# MCP960XL-L0X-RL0X_EVM_v1_Eagle7_x.net
KiCad netlist of a schematic drawn in EAGLE
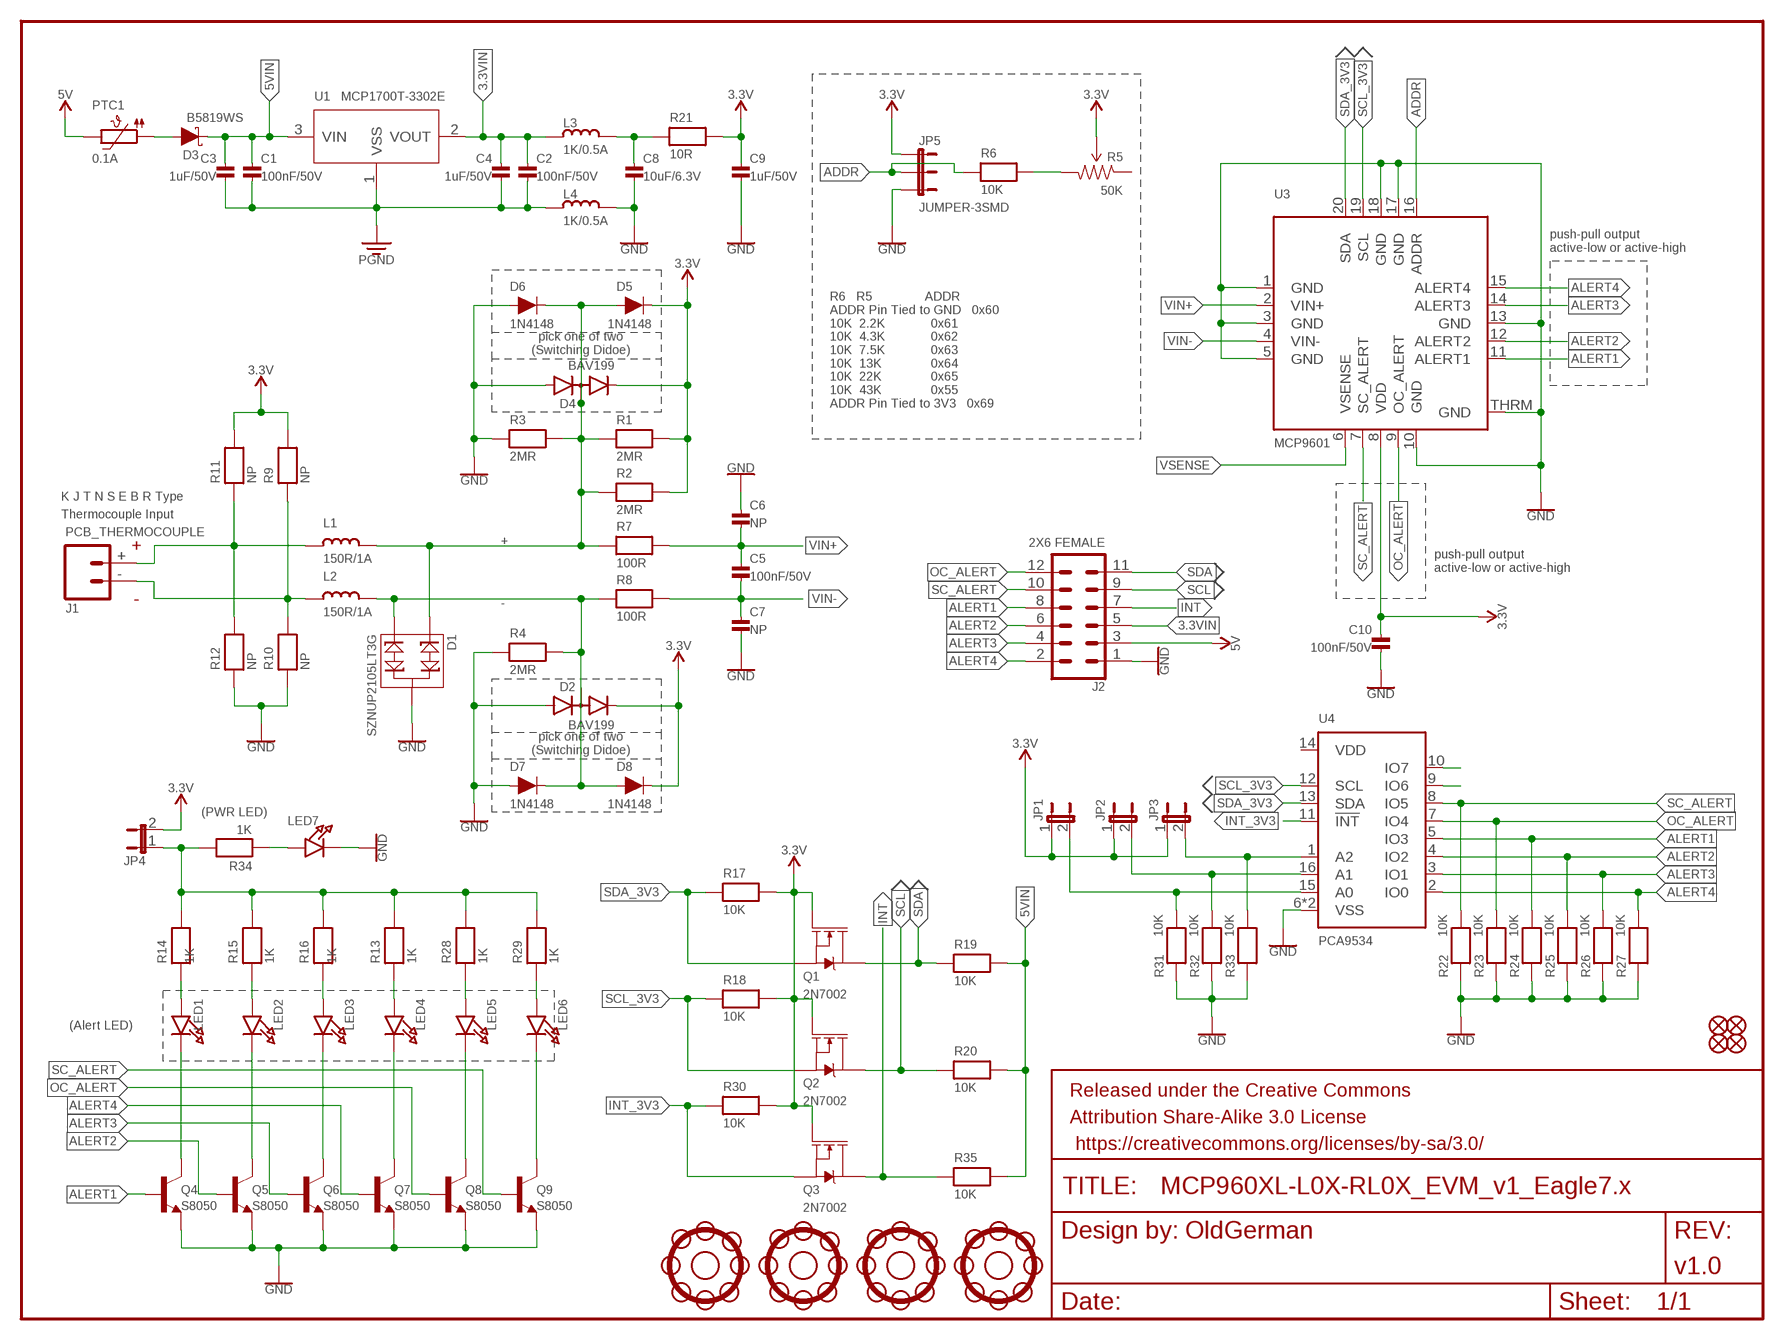
[diagram p0: schematic, sheet 1]

(export (version "E")
  (design (tool "Eeschema 10.0.6"))
  (components
    (comp (ref "C1")
      (value "100nF/50V")
      (footprint "eagle-import:0603")
      (libsource (lib "eagle-import") (part "CAP_CERAMIC0603"))
    )
    (comp (ref "C2")
      (value "100nF/50V")
      (footprint "eagle-import:0603")
      (libsource (lib "eagle-import") (part "CAP_CERAMIC0603"))
    )
    (comp (ref "C3")
      (value "1uF/50V")
      (footprint "eagle-import:0603")
      (libsource (lib "eagle-import") (part "CAP_CERAMIC0603"))
    )
    (comp (ref "C4")
      (value "1uF/50V")
      (footprint "eagle-import:0603")
      (libsource (lib "eagle-import") (part "CAP_CERAMIC0603"))
    )
    (comp (ref "C5")
      (value "100nF/50V")
      (footprint "eagle-import:0603")
      (libsource (lib "eagle-import") (part "CAP_CERAMIC0603"))
    )
    (comp (ref "C6")
      (value "NP")
      (footprint "eagle-import:0603")
      (libsource (lib "eagle-import") (part "CAP_CERAMIC0603"))
    )
    (comp (ref "C7")
      (value "NP")
      (footprint "eagle-import:0603")
      (libsource (lib "eagle-import") (part "CAP_CERAMIC0603"))
    )
    (comp (ref "C8")
      (value "10uF/6.3V")
      (footprint "eagle-import:0603")
      (libsource (lib "eagle-import") (part "CAP_CERAMIC0603"))
    )
    (comp (ref "C9")
      (value "1uF/50V")
      (footprint "eagle-import:0603")
      (libsource (lib "eagle-import") (part "CAP_CERAMIC0603"))
    )
    (comp (ref "C10")
      (value "100nF/50V")
      (footprint "eagle-import:0603")
      (libsource (lib "eagle-import") (part "CAP_CERAMIC0603"))
    )
    (comp (ref "D1")
      (value "SZNUP2105LT3G")
      (footprint "eagle-import:SOT23-3")
      (libsource (lib "eagle-import") (part "SZNUP2105LT3G"))
    )
    (comp (ref "D2")
      (value "BAV199")
      (footprint "eagle-import:SOT23-3")
      (libsource (lib "eagle-import") (part "BAV199"))
    )
    (comp (ref "D3")
      (value "B5819WS")
      (footprint "eagle-import:SOD-323")
      (libsource (lib "eagle-import") (part "DIODE_SCHOTTKYSOD323"))
    )
    (comp (ref "D4")
      (value "BAV199")
      (footprint "eagle-import:SOT23-3")
      (libsource (lib "eagle-import") (part "BAV199"))
    )
    (comp (ref "D5")
      (value "1N4148")
      (footprint "eagle-import:SOD-323")
      (libsource (lib "eagle-import") (part "DIODE"))
    )
    (comp (ref "D6")
      (value "1N4148")
      (footprint "eagle-import:SOD-323")
      (libsource (lib "eagle-import") (part "DIODE"))
    )
    (comp (ref "D7")
      (value "1N4148")
      (footprint "eagle-import:SOD-323")
      (libsource (lib "eagle-import") (part "DIODE"))
    )
    (comp (ref "D8")
      (value "1N4148")
      (footprint "eagle-import:SOD-323")
      (libsource (lib "eagle-import") (part "DIODE"))
    )
    (comp (ref "FID1")
      (value "FIDUCIAL1X2.5")
      (footprint "eagle-import:FIDUCIAL-1X2.5")
      (libsource (lib "eagle-import") (part "FIDUCIAL1X2.5"))
    )
    (comp (ref "FID2")
      (value "FIDUCIAL1X2.5")
      (footprint "eagle-import:FIDUCIAL-1X2.5")
      (libsource (lib "eagle-import") (part "FIDUCIAL1X2.5"))
    )
    (comp (ref "FID3")
      (value "FIDUCIAL1X2.5")
      (footprint "eagle-import:FIDUCIAL-1X2.5")
      (libsource (lib "eagle-import") (part "FIDUCIAL1X2.5"))
    )
    (comp (ref "FID4")
      (value "FIDUCIAL1X2.5")
      (footprint "eagle-import:FIDUCIAL-1X2.5")
      (libsource (lib "eagle-import") (part "FIDUCIAL1X2.5"))
    )
    (comp (ref "FRAME1")
      (value "FRAME-LETTER")
      (footprint "eagle-import:CREATIVE_COMMONS")
      (libsource (lib "eagle-import") (part "FRAME-LETTER"))
    )
    (comp (ref "J1")
      (value "PCB_THERMOCOUPLE")
      (footprint "eagle-import:PCC-SMP")
      (libsource (lib "eagle-import") (part "PCB_THERMOCOUPLE"))
    )
    (comp (ref "J2")
      (value "2X6 FEMALE")
      (footprint "eagle-import:2X6")
      (libsource (lib "eagle-import") (part "CONN_06X2PTH_FEMALE"))
    )
    (comp (ref "JP1")
      (value "JUMPER-2SMD-NC")
      (footprint "eagle-import:SJ_2S")
      (libsource (lib "eagle-import") (part "JUMPER-2SMD-NC"))
    )
    (comp (ref "JP2")
      (value "JUMPER-2SMD-NC")
      (footprint "eagle-import:SJ_2S")
      (libsource (lib "eagle-import") (part "JUMPER-2SMD-NC"))
    )
    (comp (ref "JP3")
      (value "JUMPER-2SMD-NC")
      (footprint "eagle-import:SJ_2S")
      (libsource (lib "eagle-import") (part "JUMPER-2SMD-NC"))
    )
    (comp (ref "JP4")
      (value "JUMPER-2SMD-NC")
      (footprint "eagle-import:SJ_2S")
      (libsource (lib "eagle-import") (part "JUMPER-2SMD-NC"))
    )
    (comp (ref "JP5")
      (value "JUMPER-3SMD")
      (footprint "eagle-import:SJ_3")
      (libsource (lib "eagle-import") (part "JUMPER-3SMD"))
    )
    (comp (ref "L1")
      (value "150R/1A")
      (footprint "eagle-import:0603")
      (libsource (lib "eagle-import") (part "INDUCTOR0603"))
    )
    (comp (ref "L2")
      (value "150R/1A")
      (footprint "eagle-import:0603")
      (libsource (lib "eagle-import") (part "INDUCTOR0603"))
    )
    (comp (ref "L3")
      (value "1K/0.5A")
      (footprint "eagle-import:0603")
      (libsource (lib "eagle-import") (part "INDUCTOR0603"))
    )
    (comp (ref "L4")
      (value "1K/0.5A")
      (footprint "eagle-import:0603")
      (libsource (lib "eagle-import") (part "INDUCTOR0603"))
    )
    (comp (ref "LED1")
      (value "LED0603")
      (footprint "eagle-import:CHIPLED_0603")
      (libsource (lib "eagle-import") (part "LED0603"))
    )
    (comp (ref "LED2")
      (value "LED0603")
      (footprint "eagle-import:CHIPLED_0603")
      (libsource (lib "eagle-import") (part "LED0603"))
    )
    (comp (ref "LED3")
      (value "LED0603")
      (footprint "eagle-import:CHIPLED_0603")
      (libsource (lib "eagle-import") (part "LED0603"))
    )
    (comp (ref "LED4")
      (value "LED0603")
      (footprint "eagle-import:CHIPLED_0603")
      (libsource (lib "eagle-import") (part "LED0603"))
    )
    (comp (ref "LED5")
      (value "LED0603")
      (footprint "eagle-import:CHIPLED_0603")
      (libsource (lib "eagle-import") (part "LED0603"))
    )
    (comp (ref "LED6")
      (value "LED0603")
      (footprint "eagle-import:CHIPLED_0603")
      (libsource (lib "eagle-import") (part "LED0603"))
    )
    (comp (ref "LED7")
      (value "LED0603")
      (footprint "eagle-import:CHIPLED_0603")
      (libsource (lib "eagle-import") (part "LED0603"))
    )
    (comp (ref "PTC1")
      (value "0.1A")
      (footprint "eagle-import:1206")
      (libsource (lib "eagle-import") (part "PTC1206"))
    )
    (comp (ref "Q1")
      (value "2N7002")
      (footprint "eagle-import:SOT23-3")
      (libsource (lib "eagle-import") (part "MOSFET-NCH-AO3404A"))
    )
    (comp (ref "Q2")
      (value "2N7002")
      (footprint "eagle-import:SOT23-3")
      (libsource (lib "eagle-import") (part "MOSFET-NCH-AO3404A"))
    )
    (comp (ref "Q3")
      (value "2N7002")
      (footprint "eagle-import:SOT23-3")
      (libsource (lib "eagle-import") (part "MOSFET-NCH-AO3404A"))
    )
    (comp (ref "Q4")
      (value "S8050")
      (footprint "eagle-import:SOT23-3")
      (libsource (lib "eagle-import") (part "TRANS_NPN-MMBT2222AL"))
    )
    (comp (ref "Q5")
      (value "S8050")
      (footprint "eagle-import:SOT23-3")
      (libsource (lib "eagle-import") (part "TRANS_NPN-MMBT2222AL"))
    )
    (comp (ref "Q6")
      (value "S8050")
      (footprint "eagle-import:SOT23-3")
      (libsource (lib "eagle-import") (part "TRANS_NPN-MMBT2222AL"))
    )
    (comp (ref "Q7")
      (value "S8050")
      (footprint "eagle-import:SOT23-3")
      (libsource (lib "eagle-import") (part "TRANS_NPN-MMBT2222AL"))
    )
    (comp (ref "Q8")
      (value "S8050")
      (footprint "eagle-import:SOT23-3")
      (libsource (lib "eagle-import") (part "TRANS_NPN-MMBT2222AL"))
    )
    (comp (ref "Q9")
      (value "S8050")
      (footprint "eagle-import:SOT23-3")
      (libsource (lib "eagle-import") (part "TRANS_NPN-MMBT2222AL"))
    )
    (comp (ref "R1")
      (value "2MR")
      (footprint "eagle-import:0603")
      (libsource (lib "eagle-import") (part "RESISTOR0603"))
    )
    (comp (ref "R2")
      (value "2MR")
      (footprint "eagle-import:0603")
      (libsource (lib "eagle-import") (part "RESISTOR0603"))
    )
    (comp (ref "R3")
      (value "2MR")
      (footprint "eagle-import:0603")
      (libsource (lib "eagle-import") (part "RESISTOR0603"))
    )
    (comp (ref "R4")
      (value "2MR")
      (footprint "eagle-import:0603")
      (libsource (lib "eagle-import") (part "RESISTOR0603"))
    )
    (comp (ref "R5")
      (value "50K")
      (footprint "eagle-import:TRIMPOT-3MM")
      (libsource (lib "eagle-import") (part "POT-SMD"))
    )
    (comp (ref "R6")
      (value "10K")
      (footprint "eagle-import:0603")
      (libsource (lib "eagle-import") (part "RESISTOR0603"))
    )
    (comp (ref "R7")
      (value "100R")
      (footprint "eagle-import:0603")
      (libsource (lib "eagle-import") (part "RESISTOR0603"))
    )
    (comp (ref "R8")
      (value "100R")
      (footprint "eagle-import:0603")
      (libsource (lib "eagle-import") (part "RESISTOR0603"))
    )
    (comp (ref "R9")
      (value "NP")
      (footprint "eagle-import:0603")
      (libsource (lib "eagle-import") (part "RESISTOR0603"))
    )
    (comp (ref "R10")
      (value "NP")
      (footprint "eagle-import:0603")
      (libsource (lib "eagle-import") (part "RESISTOR0603"))
    )
    (comp (ref "R11")
      (value "NP")
      (footprint "eagle-import:0603")
      (libsource (lib "eagle-import") (part "RESISTOR0603"))
    )
    (comp (ref "R12")
      (value "NP")
      (footprint "eagle-import:0603")
      (libsource (lib "eagle-import") (part "RESISTOR0603"))
    )
    (comp (ref "R13")
      (value "1K")
      (footprint "eagle-import:0603")
      (libsource (lib "eagle-import") (part "RESISTOR0603"))
    )
    (comp (ref "R14")
      (value "1K")
      (footprint "eagle-import:0603")
      (libsource (lib "eagle-import") (part "RESISTOR0603"))
    )
    (comp (ref "R15")
      (value "1K")
      (footprint "eagle-import:0603")
      (libsource (lib "eagle-import") (part "RESISTOR0603"))
    )
    (comp (ref "R16")
      (value "1K")
      (footprint "eagle-import:0603")
      (libsource (lib "eagle-import") (part "RESISTOR0603"))
    )
    (comp (ref "R17")
      (value "10K")
      (footprint "eagle-import:0603")
      (libsource (lib "eagle-import") (part "RESISTOR0603"))
    )
    (comp (ref "R18")
      (value "10K")
      (footprint "eagle-import:0603")
      (libsource (lib "eagle-import") (part "RESISTOR0603"))
    )
    (comp (ref "R19")
      (value "10K")
      (footprint "eagle-import:0603")
      (libsource (lib "eagle-import") (part "RESISTOR0603"))
    )
    (comp (ref "R20")
      (value "10K")
      (footprint "eagle-import:0603")
      (libsource (lib "eagle-import") (part "RESISTOR0603"))
    )
    (comp (ref "R21")
      (value "10R")
      (footprint "eagle-import:0603")
      (libsource (lib "eagle-import") (part "RESISTOR0603"))
    )
    (comp (ref "R22")
      (value "10K")
      (footprint "eagle-import:0603")
      (libsource (lib "eagle-import") (part "RESISTOR0603"))
    )
    (comp (ref "R23")
      (value "10K")
      (footprint "eagle-import:0603")
      (libsource (lib "eagle-import") (part "RESISTOR0603"))
    )
    (comp (ref "R24")
      (value "10K")
      (footprint "eagle-import:0603")
      (libsource (lib "eagle-import") (part "RESISTOR0603"))
    )
    (comp (ref "R25")
      (value "10K")
      (footprint "eagle-import:0603")
      (libsource (lib "eagle-import") (part "RESISTOR0603"))
    )
    (comp (ref "R26")
      (value "10K")
      (footprint "eagle-import:0603")
      (libsource (lib "eagle-import") (part "RESISTOR0603"))
    )
    (comp (ref "R27")
      (value "10K")
      (footprint "eagle-import:0603")
      (libsource (lib "eagle-import") (part "RESISTOR0603"))
    )
    (comp (ref "R28")
      (value "1K")
      (footprint "eagle-import:0603")
      (libsource (lib "eagle-import") (part "RESISTOR0603"))
    )
    (comp (ref "R29")
      (value "1K")
      (footprint "eagle-import:0603")
      (libsource (lib "eagle-import") (part "RESISTOR0603"))
    )
    (comp (ref "R30")
      (value "10K")
      (footprint "eagle-import:0603")
      (libsource (lib "eagle-import") (part "RESISTOR0603"))
    )
    (comp (ref "R31")
      (value "10K")
      (footprint "eagle-import:0603")
      (libsource (lib "eagle-import") (part "RESISTOR0603"))
    )
    (comp (ref "R32")
      (value "10K")
      (footprint "eagle-import:0603")
      (libsource (lib "eagle-import") (part "RESISTOR0603"))
    )
    (comp (ref "R33")
      (value "10K")
      (footprint "eagle-import:0603")
      (libsource (lib "eagle-import") (part "RESISTOR0603"))
    )
    (comp (ref "R34")
      (value "1K")
      (footprint "eagle-import:0603")
      (libsource (lib "eagle-import") (part "RESISTOR0603"))
    )
    (comp (ref "R35")
      (value "10K")
      (footprint "eagle-import:0603")
      (libsource (lib "eagle-import") (part "RESISTOR0603"))
    )
    (comp (ref "U$1")
      (value "SUN_HOLE_M3")
      (footprint "eagle-import:SUN_HOLE_M3")
      (libsource (lib "eagle-import") (part "SUN_HOLE_M3"))
    )
    (comp (ref "U$3")
      (value "SUN_HOLE_M3")
      (footprint "eagle-import:SUN_HOLE_M3")
      (libsource (lib "eagle-import") (part "SUN_HOLE_M3"))
    )
    (comp (ref "U$4")
      (value "SUN_HOLE_M3")
      (footprint "eagle-import:SUN_HOLE_M3")
      (libsource (lib "eagle-import") (part "SUN_HOLE_M3"))
    )
    (comp (ref "U$6")
      (value "SUN_HOLE_M3")
      (footprint "eagle-import:SUN_HOLE_M3")
      (libsource (lib "eagle-import") (part "SUN_HOLE_M3"))
    )
    (comp (ref "U1")
      (value "MCP1700T-3302E")
      (footprint "eagle-import:SOT23-3")
      (libsource (lib "eagle-import") (part "LDO_3PIN"))
    )
    (comp (ref "U3")
      (value "MCP9601")
      (footprint "eagle-import:VQFN20_5MM")
      (libsource (lib "eagle-import") (part "MCP9601"))
    )
    (comp (ref "U4")
      (value "PCA9534")
      (footprint "eagle-import:HVQFN16_4X4_0.65MM")
      (libsource (lib "eagle-import") (part "PCA9534"))
    )
  )
  (nets
    (net (code "1") (name "/VDD") (class "Default")
      (node (ref "U4") (pin "14") (pinfunction "VDD_14") (pintype "power_in"))
    )
    (net (code "2") (name "3.3V") (class "Default")
      (node (ref "C10") (pin "1") (pinfunction "P$1_1") (pintype "passive"))
      (node (ref "C9") (pin "1") (pinfunction "P$1_1") (pintype "passive"))
      (node (ref "D2") (pin "3") (pinfunction "C_3") (pintype "passive"))
      (node (ref "D4") (pin "3") (pinfunction "C_3") (pintype "passive"))
      (node (ref "D5") (pin "C") (pinfunction "C_C") (pintype "passive"))
      (node (ref "D8") (pin "C") (pinfunction "C_C") (pintype "passive"))
      (node (ref "JP1") (pin "1") (pinfunction "1_1") (pintype "passive"))
      (node (ref "JP2") (pin "1") (pinfunction "1_1") (pintype "passive"))
      (node (ref "JP3") (pin "1") (pinfunction "1_1") (pintype "passive"))
      (node (ref "JP4") (pin "2") (pinfunction "2_2") (pintype "passive"))
      (node (ref "JP5") (pin "1") (pinfunction "1_1") (pintype "passive"))
      (node (ref "Q1") (pin "1") (pinfunction "G_1") (pintype "bidirectional"))
      (node (ref "Q2") (pin "1") (pinfunction "G_1") (pintype "bidirectional"))
      (node (ref "Q3") (pin "1") (pinfunction "G_1") (pintype "bidirectional"))
      (node (ref "R1") (pin "2") (pinfunction "2_2") (pintype "passive"))
      (node (ref "R11") (pin "2") (pinfunction "2_2") (pintype "passive"))
      (node (ref "R17") (pin "2") (pinfunction "2_2") (pintype "passive"))
      (node (ref "R18") (pin "2") (pinfunction "2_2") (pintype "passive"))
      (node (ref "R2") (pin "2") (pinfunction "2_2") (pintype "passive"))
      (node (ref "R21") (pin "2") (pinfunction "2_2") (pintype "passive"))
      (node (ref "R30") (pin "2") (pinfunction "2_2") (pintype "passive"))
      (node (ref "R5") (pin "2") (pinfunction "WIPER_2") (pintype "passive"))
      (node (ref "R9") (pin "2") (pinfunction "2_2") (pintype "passive"))
      (node (ref "U3") (pin "8") (pinfunction "VDD_8") (pintype "bidirectional"))
    )
    (net (code "3") (name "3.3VIN") (class "Default")
      (node (ref "C2") (pin "1") (pinfunction "P$1_1") (pintype "passive"))
      (node (ref "C4") (pin "1") (pinfunction "P$1_1") (pintype "passive"))
      (node (ref "J2") (pin "5") (pinfunction "5_5") (pintype "passive"))
      (node (ref "L3") (pin "1") (pinfunction "1_1") (pintype "passive"))
      (node (ref "U1") (pin "2") (pinfunction "VOUT_2") (pintype "bidirectional"))
    )
    (net (code "4") (name "5V") (class "Default")
      (node (ref "J2") (pin "3") (pinfunction "3_3") (pintype "passive"))
      (node (ref "PTC1") (pin "2") (pinfunction "2_2") (pintype "passive"))
    )
    (net (code "5") (name "5VIN") (class "Default")
      (node (ref "C1") (pin "1") (pinfunction "P$1_1") (pintype "passive"))
      (node (ref "C3") (pin "1") (pinfunction "P$1_1") (pintype "passive"))
      (node (ref "D3") (pin "C") (pinfunction "C_C") (pintype "passive"))
      (node (ref "R19") (pin "2") (pinfunction "2_2") (pintype "passive"))
      (node (ref "R20") (pin "2") (pinfunction "2_2") (pintype "passive"))
      (node (ref "R35") (pin "2") (pinfunction "2_2") (pintype "passive"))
      (node (ref "U1") (pin "3") (pinfunction "VIN_3") (pintype "bidirectional"))
    )
    (net (code "6") (name "ADDR") (class "Default")
      (node (ref "JP5") (pin "2") (pinfunction "2_2") (pintype "passive"))
      (node (ref "R6") (pin "1") (pinfunction "1_1") (pintype "passive"))
      (node (ref "U3") (pin "16") (pinfunction "ADDR_16") (pintype "bidirectional"))
    )
    (net (code "7") (name "ALERT1") (class "Default")
      (node (ref "J2") (pin "8") (pinfunction "8_8") (pintype "passive"))
      (node (ref "Q4") (pin "1") (pinfunction "B_1") (pintype "passive"))
      (node (ref "R24") (pin "2") (pinfunction "2_2") (pintype "passive"))
      (node (ref "U3") (pin "11") (pinfunction "ALERT1_11") (pintype "bidirectional"))
      (node (ref "U4") (pin "5") (pinfunction "IO3_5") (pintype "bidirectional"))
    )
    (net (code "8") (name "ALERT2") (class "Default")
      (node (ref "J2") (pin "6") (pinfunction "6_6") (pintype "passive"))
      (node (ref "Q5") (pin "1") (pinfunction "B_1") (pintype "passive"))
      (node (ref "R25") (pin "2") (pinfunction "2_2") (pintype "passive"))
      (node (ref "U3") (pin "12") (pinfunction "ALERT2_12") (pintype "bidirectional"))
      (node (ref "U4") (pin "4") (pinfunction "IO2_4") (pintype "bidirectional"))
    )
    (net (code "9") (name "ALERT3") (class "Default")
      (node (ref "J2") (pin "4") (pinfunction "4_4") (pintype "passive"))
      (node (ref "Q6") (pin "1") (pinfunction "B_1") (pintype "passive"))
      (node (ref "R26") (pin "2") (pinfunction "2_2") (pintype "passive"))
      (node (ref "U3") (pin "14") (pinfunction "ALERT3_14") (pintype "bidirectional"))
      (node (ref "U4") (pin "3") (pinfunction "IO1_3") (pintype "bidirectional"))
    )
    (net (code "10") (name "ALERT4") (class "Default")
      (node (ref "J2") (pin "2") (pinfunction "2_2") (pintype "passive"))
      (node (ref "Q7") (pin "1") (pinfunction "B_1") (pintype "passive"))
      (node (ref "R27") (pin "2") (pinfunction "2_2") (pintype "passive"))
      (node (ref "U3") (pin "15") (pinfunction "ALERT4_15") (pintype "bidirectional"))
      (node (ref "U4") (pin "2") (pinfunction "IO0_2") (pintype "bidirectional"))
    )
    (net (code "11") (name "GND") (class "Default")
      (node (ref "C10") (pin "2") (pinfunction "P$2_2") (pintype "passive"))
      (node (ref "C6") (pin "1") (pinfunction "P$1_1") (pintype "passive"))
      (node (ref "C7") (pin "2") (pinfunction "P$2_2") (pintype "passive"))
      (node (ref "C8") (pin "2") (pinfunction "P$2_2") (pintype "passive"))
      (node (ref "C9") (pin "2") (pinfunction "P$2_2") (pintype "passive"))
      (node (ref "D1") (pin "3") (pinfunction "3_3") (pintype "bidirectional"))
      (node (ref "D2") (pin "1") (pinfunction "A_1") (pintype "passive"))
      (node (ref "D4") (pin "1") (pinfunction "A_1") (pintype "passive"))
      (node (ref "D6") (pin "A") (pinfunction "A_A") (pintype "passive"))
      (node (ref "D7") (pin "A") (pinfunction "A_A") (pintype "passive"))
      (node (ref "J2") (pin "1") (pinfunction "1_1") (pintype "passive"))
      (node (ref "JP5") (pin "3") (pinfunction "3_3") (pintype "passive"))
      (node (ref "L4") (pin "2") (pinfunction "2_2") (pintype "passive"))
      (node (ref "LED7") (pin "C") (pinfunction "C_C") (pintype "passive"))
      (node (ref "Q4") (pin "2") (pinfunction "E_2") (pintype "passive"))
      (node (ref "Q5") (pin "2") (pinfunction "E_2") (pintype "passive"))
      (node (ref "Q6") (pin "2") (pinfunction "E_2") (pintype "passive"))
      (node (ref "Q7") (pin "2") (pinfunction "E_2") (pintype "passive"))
      (node (ref "Q8") (pin "2") (pinfunction "E_2") (pintype "passive"))
      (node (ref "Q9") (pin "2") (pinfunction "E_2") (pintype "passive"))
      (node (ref "R10") (pin "1") (pinfunction "1_1") (pintype "passive"))
      (node (ref "R12") (pin "1") (pinfunction "1_1") (pintype "passive"))
      (node (ref "R22") (pin "1") (pinfunction "1_1") (pintype "passive"))
      (node (ref "R23") (pin "1") (pinfunction "1_1") (pintype "passive"))
      (node (ref "R24") (pin "1") (pinfunction "1_1") (pintype "passive"))
      (node (ref "R25") (pin "1") (pinfunction "1_1") (pintype "passive"))
      (node (ref "R26") (pin "1") (pinfunction "1_1") (pintype "passive"))
      (node (ref "R27") (pin "1") (pinfunction "1_1") (pintype "passive"))
      (node (ref "R3") (pin "1") (pinfunction "1_1") (pintype "passive"))
      (node (ref "R31") (pin "1") (pinfunction "1_1") (pintype "passive"))
      (node (ref "R32") (pin "1") (pinfunction "1_1") (pintype "passive"))
      (node (ref "R33") (pin "1") (pinfunction "1_1") (pintype "passive"))
      (node (ref "R4") (pin "1") (pinfunction "1_1") (pintype "passive"))
      (node (ref "U3") (pin "1") (pinfunction "GND_1") (pintype "bidirectional"))
      (node (ref "U3") (pin "10") (pinfunction "GND_10") (pintype "bidirectional"))
      (node (ref "U3") (pin "13") (pinfunction "GND_13") (pintype "bidirectional"))
      (node (ref "U3") (pin "17") (pinfunction "GND_17") (pintype "bidirectional"))
      (node (ref "U3") (pin "18") (pinfunction "GND_18") (pintype "bidirectional"))
      (node (ref "U3") (pin "3") (pinfunction "GND_3") (pintype "bidirectional"))
      (node (ref "U3") (pin "5") (pinfunction "GND_5") (pintype "bidirectional"))
      (node (ref "U3") (pin "THRM") (pinfunction "GND_THRM") (pintype "bidirectional"))
      (node (ref "U4") (pin "6") (pinfunction "VSS_6") (pintype "power_in"))
      (node (ref "U4") (pin "PAD") (pinfunction "VSS_PAD") (pintype "power_in"))
    )
    (net (code "12") (name "INT") (class "Default")
      (node (ref "J2") (pin "7") (pinfunction "7_7") (pintype "passive"))
      (node (ref "Q3") (pin "3") (pinfunction "D_3") (pintype "bidirectional"))
      (node (ref "R35") (pin "1") (pinfunction "1_1") (pintype "passive"))
    )
    (net (code "13") (name "INT_3V3") (class "Default")
      (node (ref "Q3") (pin "2") (pinfunction "S_2") (pintype "bidirectional"))
      (node (ref "R30") (pin "1") (pinfunction "1_1") (pintype "passive"))
      (node (ref "U4") (pin "11") (pinfunction "~{INT}_11") (pintype "open_collector"))
    )
    (net (code "14") (name "Net-(C8-P$1)") (class "Default")
      (node (ref "C8") (pin "1") (pinfunction "P$1_1") (pintype "passive"))
      (node (ref "L3") (pin "2") (pinfunction "2_2") (pintype "passive"))
      (node (ref "R21") (pin "1") (pinfunction "1_1") (pintype "passive"))
    )
    (net (code "15") (name "Net-(D2-AC)") (class "Default")
      (node (ref "D1") (pin "2") (pinfunction "2_2") (pintype "power_in"))
      (node (ref "D2") (pin "2") (pinfunction "AC_2") (pintype "passive"))
      (node (ref "D7") (pin "C") (pinfunction "C_C") (pintype "passive"))
      (node (ref "D8") (pin "A") (pinfunction "A_A") (pintype "passive"))
      (node (ref "L2") (pin "2") (pinfunction "2_2") (pintype "passive"))
      (node (ref "R4") (pin "2") (pinfunction "2_2") (pintype "passive"))
      (node (ref "R8") (pin "1") (pinfunction "1_1") (pintype "passive"))
    )
    (net (code "16") (name "Net-(D3-PadA)") (class "Default")
      (node (ref "D3") (pin "A") (pinfunction "A_A") (pintype "passive"))
      (node (ref "PTC1") (pin "1") (pinfunction "1_1") (pintype "passive"))
    )
    (net (code "17") (name "Net-(D4-AC)") (class "Default")
      (node (ref "D1") (pin "1") (pinfunction "1_1") (pintype "power_in"))
      (node (ref "D4") (pin "2") (pinfunction "AC_2") (pintype "passive"))
      (node (ref "D5") (pin "A") (pinfunction "A_A") (pintype "passive"))
      (node (ref "D6") (pin "C") (pinfunction "C_C") (pintype "passive"))
      (node (ref "L1") (pin "2") (pinfunction "2_2") (pintype "passive"))
      (node (ref "R1") (pin "1") (pinfunction "1_1") (pintype "passive"))
      (node (ref "R2") (pin "1") (pinfunction "1_1") (pintype "passive"))
      (node (ref "R3") (pin "2") (pinfunction "2_2") (pintype "passive"))
      (node (ref "R7") (pin "1") (pinfunction "1_1") (pintype "passive"))
    )
    (net (code "18") (name "Net-(J1-Pad+)") (class "Default")
      (node (ref "J1") (pin "+") (pinfunction "+_+") (pintype "passive"))
      (node (ref "L1") (pin "1") (pinfunction "1_1") (pintype "passive"))
      (node (ref "R11") (pin "1") (pinfunction "1_1") (pintype "passive"))
      (node (ref "R12") (pin "2") (pinfunction "2_2") (pintype "passive"))
    )
    (net (code "19") (name "Net-(J1-Pad-)") (class "Default")
      (node (ref "J1") (pin "-") (pinfunction "-_-") (pintype "passive"))
      (node (ref "L2") (pin "1") (pinfunction "1_1") (pintype "passive"))
      (node (ref "R10") (pin "2") (pinfunction "2_2") (pintype "passive"))
      (node (ref "R9") (pin "1") (pinfunction "1_1") (pintype "passive"))
    )
    (net (code "20") (name "Net-(JP4-Pad1)") (class "Default")
      (node (ref "JP4") (pin "1") (pinfunction "1_1") (pintype "passive"))
      (node (ref "R13") (pin "2") (pinfunction "2_2") (pintype "passive"))
      (node (ref "R14") (pin "2") (pinfunction "2_2") (pintype "passive"))
      (node (ref "R15") (pin "2") (pinfunction "2_2") (pintype "passive"))
      (node (ref "R16") (pin "2") (pinfunction "2_2") (pintype "passive"))
      (node (ref "R28") (pin "2") (pinfunction "2_2") (pintype "passive"))
      (node (ref "R29") (pin "2") (pinfunction "2_2") (pintype "passive"))
      (node (ref "R34") (pin "2") (pinfunction "2_2") (pintype "passive"))
    )
    (net (code "21") (name "Net-(LED1-PadA)") (class "Default")
      (node (ref "LED1") (pin "A") (pinfunction "A_A") (pintype "passive"))
      (node (ref "R14") (pin "1") (pinfunction "1_1") (pintype "passive"))
    )
    (net (code "22") (name "Net-(LED2-PadA)") (class "Default")
      (node (ref "LED2") (pin "A") (pinfunction "A_A") (pintype "passive"))
      (node (ref "R15") (pin "1") (pinfunction "1_1") (pintype "passive"))
    )
    (net (code "23") (name "Net-(LED3-PadA)") (class "Default")
      (node (ref "LED3") (pin "A") (pinfunction "A_A") (pintype "passive"))
      (node (ref "R16") (pin "1") (pinfunction "1_1") (pintype "passive"))
    )
    (net (code "24") (name "Net-(LED4-PadA)") (class "Default")
      (node (ref "LED4") (pin "A") (pinfunction "A_A") (pintype "passive"))
      (node (ref "R13") (pin "1") (pinfunction "1_1") (pintype "passive"))
    )
    (net (code "25") (name "Net-(LED5-PadA)") (class "Default")
      (node (ref "LED5") (pin "A") (pinfunction "A_A") (pintype "passive"))
      (node (ref "R28") (pin "1") (pinfunction "1_1") (pintype "passive"))
    )
    (net (code "26") (name "Net-(LED6-PadA)") (class "Default")
      (node (ref "LED6") (pin "A") (pinfunction "A_A") (pintype "passive"))
      (node (ref "R29") (pin "1") (pinfunction "1_1") (pintype "passive"))
    )
    (net (code "27") (name "Net-(LED7-PadA)") (class "Default")
      (node (ref "LED7") (pin "A") (pinfunction "A_A") (pintype "passive"))
      (node (ref "R34") (pin "1") (pinfunction "1_1") (pintype "passive"))
    )
    (net (code "28") (name "Net-(Q4-C)") (class "Default")
      (node (ref "LED1") (pin "C") (pinfunction "C_C") (pintype "passive"))
      (node (ref "Q4") (pin "3") (pinfunction "C_3") (pintype "passive"))
    )
    (net (code "29") (name "Net-(Q5-C)") (class "Default")
      (node (ref "LED2") (pin "C") (pinfunction "C_C") (pintype "passive"))
      (node (ref "Q5") (pin "3") (pinfunction "C_3") (pintype "passive"))
    )
    (net (code "30") (name "Net-(Q6-C)") (class "Default")
      (node (ref "LED3") (pin "C") (pinfunction "C_C") (pintype "passive"))
      (node (ref "Q6") (pin "3") (pinfunction "C_3") (pintype "passive"))
    )
    (net (code "31") (name "Net-(Q7-C)") (class "Default")
      (node (ref "LED4") (pin "C") (pinfunction "C_C") (pintype "passive"))
      (node (ref "Q7") (pin "3") (pinfunction "C_3") (pintype "passive"))
    )
    (net (code "32") (name "Net-(Q8-C)") (class "Default")
      (node (ref "LED5") (pin "C") (pinfunction "C_C") (pintype "passive"))
      (node (ref "Q8") (pin "3") (pinfunction "C_3") (pintype "passive"))
    )
    (net (code "33") (name "Net-(Q9-C)") (class "Default")
      (node (ref "LED6") (pin "C") (pinfunction "C_C") (pintype "passive"))
      (node (ref "Q9") (pin "3") (pinfunction "C_3") (pintype "passive"))
    )
    (net (code "34") (name "Net-(R5-CW)") (class "Default")
      (node (ref "R5") (pin "1") (pinfunction "CW_1") (pintype "passive"))
      (node (ref "R6") (pin "2") (pinfunction "2_2") (pintype "passive"))
    )
    (net (code "35") (name "Net-(U4-A0)") (class "Default")
      (node (ref "JP1") (pin "2") (pinfunction "2_2") (pintype "passive"))
      (node (ref "R31") (pin "2") (pinfunction "2_2") (pintype "passive"))
      (node (ref "U4") (pin "15") (pinfunction "A0_15") (pintype "input"))
    )
    (net (code "36") (name "Net-(U4-A1)") (class "Default")
      (node (ref "JP2") (pin "2") (pinfunction "2_2") (pintype "passive"))
      (node (ref "R32") (pin "2") (pinfunction "2_2") (pintype "passive"))
      (node (ref "U4") (pin "16") (pinfunction "A1_16") (pintype "input"))
    )
    (net (code "37") (name "Net-(U4-A2)") (class "Default")
      (node (ref "JP3") (pin "2") (pinfunction "2_2") (pintype "passive"))
      (node (ref "R33") (pin "2") (pinfunction "2_2") (pintype "passive"))
      (node (ref "U4") (pin "1") (pinfunction "A2_1") (pintype "input"))
    )
    (net (code "38") (name "OC_ALERT") (class "Default")
      (node (ref "J2") (pin "12") (pinfunction "12_12") (pintype "passive"))
      (node (ref "Q8") (pin "1") (pinfunction "B_1") (pintype "passive"))
      (node (ref "R23") (pin "2") (pinfunction "2_2") (pintype "passive"))
      (node (ref "U3") (pin "9") (pinfunction "OC_ALERT_9") (pintype "bidirectional"))
      (node (ref "U4") (pin "7") (pinfunction "IO4_7") (pintype "bidirectional"))
    )
    (net (code "39") (name "PGND") (class "Default")
      (node (ref "C1") (pin "2") (pinfunction "P$2_2") (pintype "passive"))
      (node (ref "C2") (pin "2") (pinfunction "P$2_2") (pintype "passive"))
      (node (ref "C3") (pin "2") (pinfunction "P$2_2") (pintype "passive"))
      (node (ref "C4") (pin "2") (pinfunction "P$2_2") (pintype "passive"))
      (node (ref "L4") (pin "1") (pinfunction "1_1") (pintype "passive"))
      (node (ref "U1") (pin "1") (pinfunction "VSS_1") (pintype "bidirectional"))
    )
    (net (code "40") (name "SCL") (class "Default")
      (node (ref "J2") (pin "9") (pinfunction "9_9") (pintype "passive"))
      (node (ref "Q2") (pin "3") (pinfunction "D_3") (pintype "bidirectional"))
      (node (ref "R20") (pin "1") (pinfunction "1_1") (pintype "passive"))
    )
    (net (code "41") (name "SCL_3V3") (class "Default")
      (node (ref "Q2") (pin "2") (pinfunction "S_2") (pintype "bidirectional"))
      (node (ref "R18") (pin "1") (pinfunction "1_1") (pintype "passive"))
      (node (ref "U3") (pin "19") (pinfunction "SCL_19") (pintype "bidirectional"))
      (node (ref "U4") (pin "12") (pinfunction "SCL_12") (pintype "input"))
    )
    (net (code "42") (name "SC_ALERT") (class "Default")
      (node (ref "J2") (pin "10") (pinfunction "10_10") (pintype "passive"))
      (node (ref "Q9") (pin "1") (pinfunction "B_1") (pintype "passive"))
      (node (ref "R22") (pin "2") (pinfunction "2_2") (pintype "passive"))
      (node (ref "U3") (pin "7") (pinfunction "SC_ALERT_7") (pintype "bidirectional"))
      (node (ref "U4") (pin "8") (pinfunction "IO5_8") (pintype "bidirectional"))
    )
    (net (code "43") (name "SDA") (class "Default")
      (node (ref "J2") (pin "11") (pinfunction "11_11") (pintype "passive"))
      (node (ref "Q1") (pin "3") (pinfunction "D_3") (pintype "bidirectional"))
      (node (ref "R19") (pin "1") (pinfunction "1_1") (pintype "passive"))
    )
    (net (code "44") (name "SDA_3V3") (class "Default")
      (node (ref "Q1") (pin "2") (pinfunction "S_2") (pintype "bidirectional"))
      (node (ref "R17") (pin "1") (pinfunction "1_1") (pintype "passive"))
      (node (ref "U3") (pin "20") (pinfunction "SDA_20") (pintype "bidirectional"))
      (node (ref "U4") (pin "13") (pinfunction "SDA_13") (pintype "bidirectional"))
    )
    (net (code "45") (name "VIN+") (class "Default")
      (node (ref "C5") (pin "1") (pinfunction "P$1_1") (pintype "passive"))
      (node (ref "C6") (pin "2") (pinfunction "P$2_2") (pintype "passive"))
      (node (ref "R7") (pin "2") (pinfunction "2_2") (pintype "passive"))
      (node (ref "U3") (pin "2") (pinfunction "VIN+_2") (pintype "bidirectional"))
    )
    (net (code "46") (name "VIN-") (class "Default")
      (node (ref "C5") (pin "2") (pinfunction "P$2_2") (pintype "passive"))
      (node (ref "C7") (pin "1") (pinfunction "P$1_1") (pintype "passive"))
      (node (ref "R8") (pin "2") (pinfunction "2_2") (pintype "passive"))
      (node (ref "U3") (pin "4") (pinfunction "VIN-_4") (pintype "bidirectional"))
    )
    (net (code "47") (name "VSENSE") (class "Default")
      (node (ref "U3") (pin "6") (pinfunction "VSENSE_6") (pintype "bidirectional"))
    )
    (net (code "48") (name "unconnected-(R5-CCW-Pad3)") (class "Default")
      (node (ref "R5") (pin "3") (pinfunction "CCW_3") (pintype "passive"))
    )
    (net (code "49") (name "unconnected-(U4-IO6-Pad9)") (class "Default")
      (node (ref "U4") (pin "9") (pinfunction "IO6_9") (pintype "bidirectional"))
    )
    (net (code "50") (name "unconnected-(U4-IO7-Pad10)") (class "Default")
      (node (ref "U4") (pin "10") (pinfunction "IO7_10") (pintype "bidirectional"))
    )
  )
)
